# Counter2DigitRG.net
KiCad netlist of a schematic drawn in EAGLE
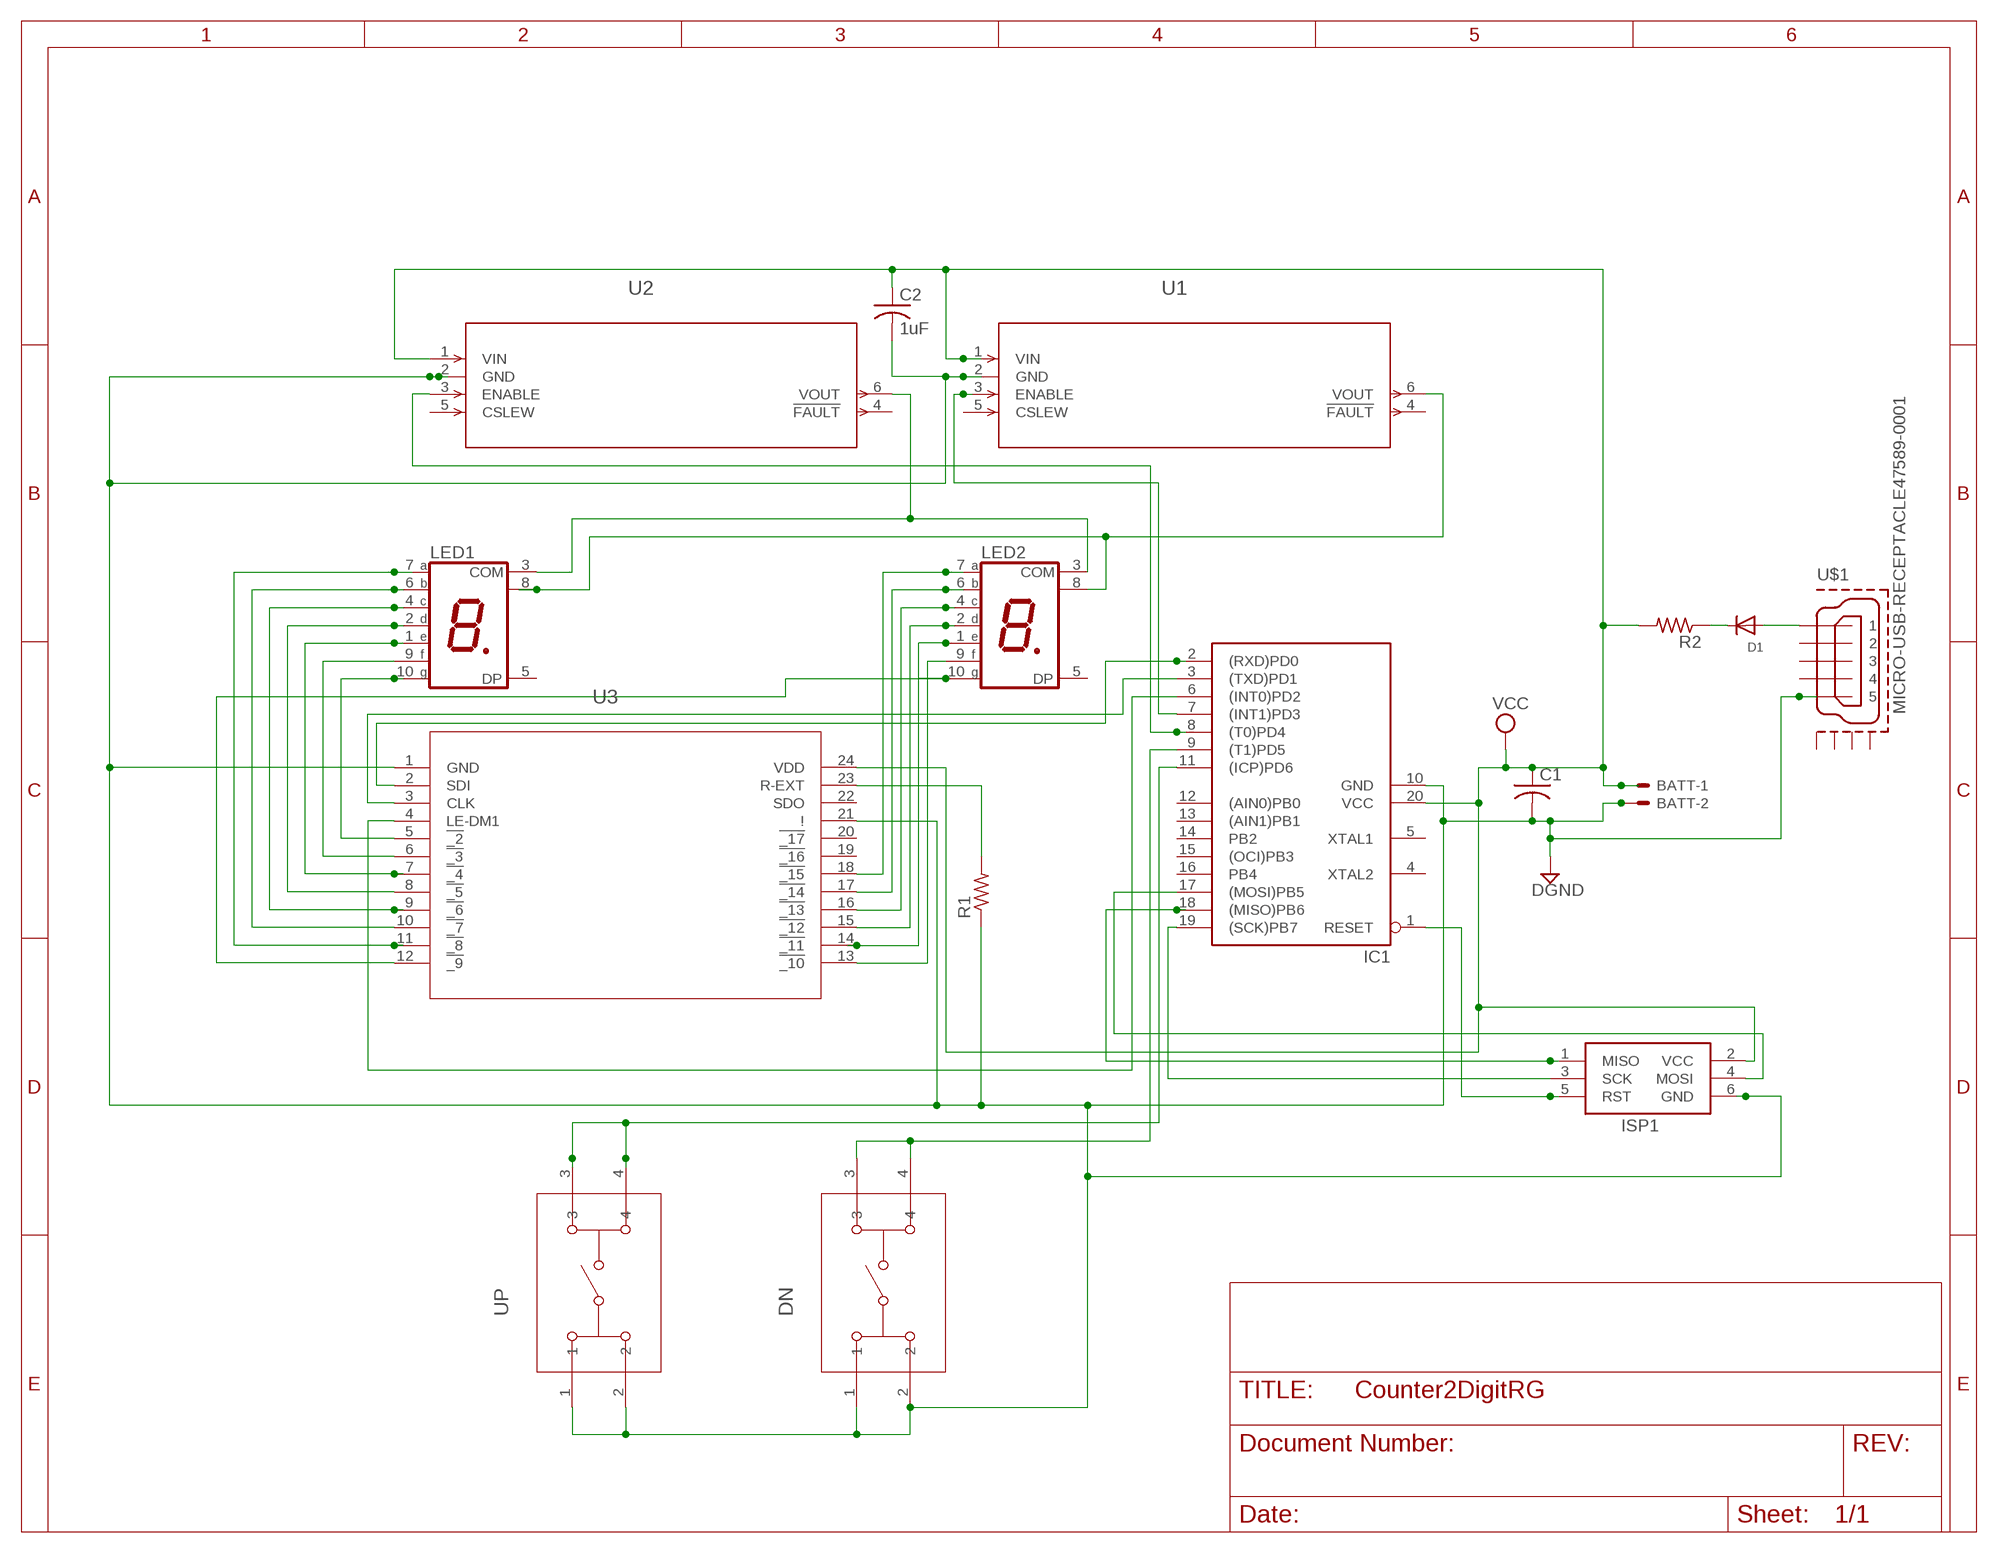
[diagram p0: schematic, sheet 1]

(export (version "E")
  (design (tool "Eeschema 10.0.6"))
  (components
    (comp (ref "BATT")
      (value "22-23-2021")
      (footprint "eagle-import:22-23-2021")
      (fields (field (name "MF") "MOLEX"))
      (libsource (lib "eagle-import") (part "22-23-2021"))
    )
    (comp (ref "C1")
      (value "C-USC0805")
      (footprint "eagle-import:C0805")
      (libsource (lib "eagle-import") (part "C-USC0805"))
    )
    (comp (ref "C2")
      (value "1uF")
      (footprint "eagle-import:C0805")
      (libsource (lib "eagle-import") (part "C-USC0805"))
    )
    (comp (ref "D1")
      (value "DIODESOD-123")
      (footprint "eagle-import:SOD-123")
      (libsource (lib "eagle-import") (part "DIODESOD-123"))
    )
    (comp (ref "DN")
      (value "1-1825910-4")
      (footprint "eagle-import:SW4_1825910-D")
      (fields (field (name "COPYRIGHT") "Copyright (C) 2016 Accelerated Designs. All rights reserved"))
      (libsource (lib "eagle-import") (part "1-1825910-4"))
    )
    (comp (ref "IC1")
      (value "AT90S2313S")
      (footprint "eagle-import:SO20L")
      (libsource (lib "eagle-import") (part "AT90S2313S"))
    )
    (comp (ref "ISP1")
      (value "AVRISP-6")
      (footprint "eagle-import:AVRISP")
      (libsource (lib "eagle-import") (part "AVRISP-6"))
    )
    (comp (ref "LED1")
      (value "7-SEG_SA56-11")
      (footprint "eagle-import:SA56-11")
      (libsource (lib "eagle-import") (part "7-SEG_SA56-11"))
    )
    (comp (ref "LED2")
      (value "7-SEG_SA56-11")
      (footprint "eagle-import:SA56-11")
      (libsource (lib "eagle-import") (part "7-SEG_SA56-11"))
    )
    (comp (ref "R1")
      (value "R-US_M0805")
      (footprint "eagle-import:M0805")
      (libsource (lib "eagle-import") (part "R-US_M0805"))
    )
    (comp (ref "R2")
      (value "R-US_M0805")
      (footprint "eagle-import:M0805")
      (libsource (lib "eagle-import") (part "R-US_M0805"))
    )
    (comp (ref "U$1")
      (value "MICRO-USB-RECEPTACLE47589-0001")
      (footprint "eagle-import:47589-0001")
      (libsource (lib "eagle-import") (part "MICRO-USB-RECEPTACLE47589-0001"))
    )
    (comp (ref "U1")
      (value "MIC2005A-2YM6-TR")
      (footprint "eagle-import:SOT-23-6_M6")
      (fields (field (name "COPYRIGHT") "Copyright (C) 2018 Accelerated Designs. All rights reserved"))
      (libsource (lib "eagle-import") (part "MIC2005A-2YM6-TR"))
    )
    (comp (ref "U2")
      (value "MIC2005A-2YM6-TR")
      (footprint "eagle-import:SOT-23-6_M6")
      (fields (field (name "COPYRIGHT") "Copyright (C) 2018 Accelerated Designs. All rights reserved"))
      (libsource (lib "eagle-import") (part "MIC2005A-2YM6-TR"))
    )
    (comp (ref "U3")
      (value "STP16CPC26MTRSO-24-M")
      (footprint "eagle-import:SO-24-M")
      (fields (field (name "MANUFACTURER_PART_NUMBER") "STP16CPC26MTR"))
      (libsource (lib "eagle-import") (part "STP16CPC26MTRSO-24-M"))
    )
    (comp (ref "UP")
      (value "1-1825910-4")
      (footprint "eagle-import:SW4_1825910-D")
      (fields (field (name "COPYRIGHT") "Copyright (C) 2016 Accelerated Designs. All rights reserved"))
      (libsource (lib "eagle-import") (part "1-1825910-4"))
    )
  )
  (nets
    (net (code "1") (name "DGND") (class "Default")
      (node (ref "BATT") (pin "2") (pinfunction "S_2") (pintype "passive"))
      (node (ref "C1") (pin "2") (pinfunction "2_2") (pintype "passive"))
      (node (ref "C2") (pin "2") (pinfunction "2_2") (pintype "passive"))
      (node (ref "DN") (pin "1") (pinfunction "1_1") (pintype "passive"))
      (node (ref "DN") (pin "2") (pinfunction "2_2") (pintype "passive"))
      (node (ref "IC1") (pin "10") (pinfunction "GND_10") (pintype "power_in"))
      (node (ref "ISP1") (pin "6") (pinfunction "GND_6") (pintype "power_in"))
      (node (ref "R1") (pin "1") (pinfunction "1_1") (pintype "passive"))
      (node (ref "U$1") (pin "5") (pinfunction "5_5") (pintype "input"))
      (node (ref "U1") (pin "2") (pinfunction "GND_2") (pintype "power_in"))
      (node (ref "U2") (pin "2") (pinfunction "GND_2") (pintype "power_in"))
      (node (ref "U3") (pin "1") (pinfunction "GND_1") (pintype "power_in"))
      (node (ref "U3") (pin "21") (pinfunction "~_21") (pintype "input"))
      (node (ref "UP") (pin "1") (pinfunction "1_1") (pintype "passive"))
      (node (ref "UP") (pin "2") (pinfunction "2_2") (pintype "passive"))
    )
    (net (code "2") (name "Net-(D1-PadA)") (class "Default")
      (node (ref "D1") (pin "A") (pinfunction "A_A") (pintype "passive"))
      (node (ref "U$1") (pin "1") (pinfunction "1_1") (pintype "input"))
    )
    (net (code "3") (name "Net-(D1-PadC)") (class "Default")
      (node (ref "D1") (pin "C") (pinfunction "C_C") (pintype "passive"))
      (node (ref "R2") (pin "1") (pinfunction "1_1") (pintype "passive"))
    )
    (net (code "4") (name "Net-(IC1-(ICP)PD6)") (class "Default")
      (node (ref "IC1") (pin "11") (pinfunction "(ICP)PD6_11") (pintype "bidirectional"))
      (node (ref "UP") (pin "3") (pinfunction "3_3") (pintype "passive"))
      (node (ref "UP") (pin "4") (pinfunction "4_4") (pintype "passive"))
    )
    (net (code "5") (name "Net-(IC1-(INT0)PD2)") (class "Default")
      (node (ref "IC1") (pin "6") (pinfunction "(INT0)PD2_6") (pintype "bidirectional"))
      (node (ref "U3") (pin "4") (pinfunction "LE-DM1_4") (pintype "input"))
    )
    (net (code "6") (name "Net-(IC1-(INT1)PD3)") (class "Default")
      (node (ref "IC1") (pin "7") (pinfunction "(INT1)PD3_7") (pintype "bidirectional"))
      (node (ref "U1") (pin "3") (pinfunction "ENABLE_3") (pintype "input"))
    )
    (net (code "7") (name "Net-(IC1-(MISO)PB6)") (class "Default")
      (node (ref "IC1") (pin "18") (pinfunction "(MISO)PB6_18") (pintype "bidirectional"))
      (node (ref "ISP1") (pin "1") (pinfunction "MISO_1") (pintype "input"))
    )
    (net (code "8") (name "Net-(IC1-(MOSI)PB5)") (class "Default")
      (node (ref "IC1") (pin "17") (pinfunction "(MOSI)PB5_17") (pintype "bidirectional"))
      (node (ref "ISP1") (pin "4") (pinfunction "MOSI_4") (pintype "output"))
    )
    (net (code "9") (name "Net-(IC1-(RXD)PD0)") (class "Default")
      (node (ref "IC1") (pin "2") (pinfunction "(RXD)PD0_2") (pintype "bidirectional"))
      (node (ref "U3") (pin "2") (pinfunction "SDI_2") (pintype "input"))
    )
    (net (code "10") (name "Net-(IC1-(SCK)PB7)") (class "Default")
      (node (ref "IC1") (pin "19") (pinfunction "(SCK)PB7_19") (pintype "bidirectional"))
      (node (ref "ISP1") (pin "3") (pinfunction "SCK_3") (pintype "output"))
    )
    (net (code "11") (name "Net-(IC1-(T0)PD4)") (class "Default")
      (node (ref "IC1") (pin "8") (pinfunction "(T0)PD4_8") (pintype "bidirectional"))
      (node (ref "U2") (pin "3") (pinfunction "ENABLE_3") (pintype "input"))
    )
    (net (code "12") (name "Net-(IC1-(T1)PD5)") (class "Default")
      (node (ref "DN") (pin "3") (pinfunction "3_3") (pintype "passive"))
      (node (ref "DN") (pin "4") (pinfunction "4_4") (pintype "passive"))
      (node (ref "IC1") (pin "9") (pinfunction "(T1)PD5_9") (pintype "bidirectional"))
    )
    (net (code "13") (name "Net-(IC1-(TXD)PD1)") (class "Default")
      (node (ref "IC1") (pin "3") (pinfunction "(TXD)PD1_3") (pintype "bidirectional"))
      (node (ref "U3") (pin "3") (pinfunction "CLK_3") (pintype "input"))
    )
    (net (code "14") (name "Net-(IC1-RESET)") (class "Default")
      (node (ref "IC1") (pin "1") (pinfunction "RESET_1") (pintype "bidirectional"))
      (node (ref "ISP1") (pin "5") (pinfunction "RST_5") (pintype "output"))
    )
    (net (code "15") (name "Net-(LED1-A)") (class "Default")
      (node (ref "LED1") (pin "7") (pinfunction "A_7") (pintype "passive"))
      (node (ref "U3") (pin "11") (pinfunction "~{_8}_11") (pintype "output"))
    )
    (net (code "16") (name "Net-(LED1-B)") (class "Default")
      (node (ref "LED1") (pin "6") (pinfunction "B_6") (pintype "passive"))
      (node (ref "U3") (pin "10") (pinfunction "~{_7}_10") (pintype "output"))
    )
    (net (code "17") (name "Net-(LED1-C)") (class "Default")
      (node (ref "LED1") (pin "4") (pinfunction "C_4") (pintype "passive"))
      (node (ref "U3") (pin "9") (pinfunction "~{_6}_9") (pintype "output"))
    )
    (net (code "18") (name "Net-(LED1-D)") (class "Default")
      (node (ref "LED1") (pin "2") (pinfunction "D_2") (pintype "passive"))
      (node (ref "U3") (pin "8") (pinfunction "~{_5}_8") (pintype "output"))
    )
    (net (code "19") (name "Net-(LED1-E)") (class "Default")
      (node (ref "LED1") (pin "1") (pinfunction "E_1") (pintype "passive"))
      (node (ref "U3") (pin "7") (pinfunction "~{_4}_7") (pintype "output"))
    )
    (net (code "20") (name "Net-(LED1-F)") (class "Default")
      (node (ref "LED1") (pin "9") (pinfunction "F_9") (pintype "passive"))
      (node (ref "U3") (pin "6") (pinfunction "~{_3}_6") (pintype "output"))
    )
    (net (code "21") (name "Net-(LED1-G)") (class "Default")
      (node (ref "LED1") (pin "10") (pinfunction "G_10") (pintype "passive"))
      (node (ref "U3") (pin "5") (pinfunction "~{_2}_5") (pintype "output"))
    )
    (net (code "22") (name "Net-(LED2-A)") (class "Default")
      (node (ref "LED2") (pin "7") (pinfunction "A_7") (pintype "passive"))
      (node (ref "U3") (pin "18") (pinfunction "~{_15}_18") (pintype "output"))
    )
    (net (code "23") (name "Net-(LED2-B)") (class "Default")
      (node (ref "LED2") (pin "6") (pinfunction "B_6") (pintype "passive"))
      (node (ref "U3") (pin "17") (pinfunction "~{_14}_17") (pintype "output"))
    )
    (net (code "24") (name "Net-(LED2-C)") (class "Default")
      (node (ref "LED2") (pin "4") (pinfunction "C_4") (pintype "passive"))
      (node (ref "U3") (pin "16") (pinfunction "~{_13}_16") (pintype "output"))
    )
    (net (code "25") (name "Net-(LED2-D)") (class "Default")
      (node (ref "LED2") (pin "2") (pinfunction "D_2") (pintype "passive"))
      (node (ref "U3") (pin "15") (pinfunction "~{_12}_15") (pintype "output"))
    )
    (net (code "26") (name "Net-(LED2-E)") (class "Default")
      (node (ref "LED2") (pin "1") (pinfunction "E_1") (pintype "passive"))
      (node (ref "U3") (pin "14") (pinfunction "~{_11}_14") (pintype "output"))
    )
    (net (code "27") (name "Net-(LED2-F)") (class "Default")
      (node (ref "LED2") (pin "9") (pinfunction "F_9") (pintype "passive"))
      (node (ref "U3") (pin "13") (pinfunction "~{_10}_13") (pintype "output"))
    )
    (net (code "28") (name "Net-(LED2-G)") (class "Default")
      (node (ref "LED2") (pin "10") (pinfunction "G_10") (pintype "passive"))
      (node (ref "U3") (pin "12") (pinfunction "~{_9}_12") (pintype "output"))
    )
    (net (code "29") (name "Net-(U1-VOUT)") (class "Default")
      (node (ref "LED1") (pin "8") (pinfunction "COM_8") (pintype "passive"))
      (node (ref "LED2") (pin "8") (pinfunction "COM_8") (pintype "passive"))
      (node (ref "U1") (pin "6") (pinfunction "VOUT_6") (pintype "output"))
    )
    (net (code "30") (name "Net-(U2-VOUT)") (class "Default")
      (node (ref "LED1") (pin "3") (pinfunction "COM_3") (pintype "passive"))
      (node (ref "LED2") (pin "3") (pinfunction "COM_3") (pintype "passive"))
      (node (ref "U2") (pin "6") (pinfunction "VOUT_6") (pintype "output"))
    )
    (net (code "31") (name "Net-(U3-R-EXT)") (class "Default")
      (node (ref "R1") (pin "2") (pinfunction "2_2") (pintype "passive"))
      (node (ref "U3") (pin "23") (pinfunction "R-EXT_23") (pintype "input"))
    )
    (net (code "32") (name "VCC") (class "Default")
      (node (ref "BATT") (pin "1") (pinfunction "S_1") (pintype "passive"))
      (node (ref "C1") (pin "1") (pinfunction "1_1") (pintype "passive"))
      (node (ref "C2") (pin "1") (pinfunction "1_1") (pintype "passive"))
      (node (ref "IC1") (pin "20") (pinfunction "VCC_20") (pintype "power_in"))
      (node (ref "ISP1") (pin "2") (pinfunction "VCC_2") (pintype "power_in"))
      (node (ref "R2") (pin "2") (pinfunction "2_2") (pintype "passive"))
      (node (ref "U1") (pin "1") (pinfunction "VIN_1") (pintype "input"))
      (node (ref "U2") (pin "1") (pinfunction "VIN_1") (pintype "input"))
      (node (ref "U3") (pin "24") (pinfunction "VDD_24") (pintype "power_in"))
    )
    (net (code "33") (name "unconnected-(IC1-(AIN0)PB0-Pad12)") (class "Default")
      (node (ref "IC1") (pin "12") (pinfunction "(AIN0)PB0_12") (pintype "bidirectional"))
    )
    (net (code "34") (name "unconnected-(IC1-(AIN1)PB1-Pad13)") (class "Default")
      (node (ref "IC1") (pin "13") (pinfunction "(AIN1)PB1_13") (pintype "bidirectional"))
    )
    (net (code "35") (name "unconnected-(IC1-(OCI)PB3-Pad15)") (class "Default")
      (node (ref "IC1") (pin "15") (pinfunction "(OCI)PB3_15") (pintype "bidirectional"))
    )
    (net (code "36") (name "unconnected-(IC1-PB2-Pad14)") (class "Default")
      (node (ref "IC1") (pin "14") (pinfunction "PB2_14") (pintype "bidirectional"))
    )
    (net (code "37") (name "unconnected-(IC1-PB4-Pad16)") (class "Default")
      (node (ref "IC1") (pin "16") (pinfunction "PB4_16") (pintype "bidirectional"))
    )
    (net (code "38") (name "unconnected-(IC1-XTAL1-Pad5)") (class "Default")
      (node (ref "IC1") (pin "5") (pinfunction "XTAL1_5") (pintype "bidirectional"))
    )
    (net (code "39") (name "unconnected-(IC1-XTAL2-Pad4)") (class "Default")
      (node (ref "IC1") (pin "4") (pinfunction "XTAL2_4") (pintype "bidirectional"))
    )
    (net (code "40") (name "unconnected-(LED1-DP-Pad5)") (class "Default")
      (node (ref "LED1") (pin "5") (pinfunction "DP_5") (pintype "passive"))
    )
    (net (code "41") (name "unconnected-(LED2-DP-Pad5)") (class "Default")
      (node (ref "LED2") (pin "5") (pinfunction "DP_5") (pintype "passive"))
    )
    (net (code "42") (name "unconnected-(U$1-GND1-PadCASING1)") (class "Default")
      (node (ref "U$1") (pin "CASING1") (pinfunction "GND1_CASING1") (pintype "bidirectional"))
    )
    (net (code "43") (name "unconnected-(U$1-GND2-PadCASING2)") (class "Default")
      (node (ref "U$1") (pin "CASING2") (pinfunction "GND2_CASING2") (pintype "bidirectional"))
    )
    (net (code "44") (name "unconnected-(U$1-GND3-PadCASING3)") (class "Default")
      (node (ref "U$1") (pin "CASING3") (pinfunction "GND3_CASING3") (pintype "bidirectional"))
    )
    (net (code "45") (name "unconnected-(U$1-GND4-PadCASING4)") (class "Default")
      (node (ref "U$1") (pin "CASING4") (pinfunction "GND4_CASING4") (pintype "bidirectional"))
    )
    (net (code "46") (name "unconnected-(U$1-Pad2)") (class "Default")
      (node (ref "U$1") (pin "2") (pinfunction "2_2") (pintype "input"))
    )
    (net (code "47") (name "unconnected-(U$1-Pad3)") (class "Default")
      (node (ref "U$1") (pin "3") (pinfunction "3_3") (pintype "input"))
    )
    (net (code "48") (name "unconnected-(U$1-Pad4)") (class "Default")
      (node (ref "U$1") (pin "4") (pinfunction "4_4") (pintype "input"))
    )
    (net (code "49") (name "unconnected-(U1-CSLEW-Pad5)") (class "Default")
      (node (ref "U1") (pin "5") (pinfunction "CSLEW_5") (pintype "input"))
    )
    (net (code "50") (name "unconnected-(U1-~{FAULT}-Pad4)") (class "Default")
      (node (ref "U1") (pin "4") (pinfunction "~{FAULT}_4") (pintype "output"))
    )
    (net (code "51") (name "unconnected-(U2-CSLEW-Pad5)") (class "Default")
      (node (ref "U2") (pin "5") (pinfunction "CSLEW_5") (pintype "input"))
    )
    (net (code "52") (name "unconnected-(U2-~{FAULT}-Pad4)") (class "Default")
      (node (ref "U2") (pin "4") (pinfunction "~{FAULT}_4") (pintype "output"))
    )
    (net (code "53") (name "unconnected-(U3-SDO-Pad22)") (class "Default")
      (node (ref "U3") (pin "22") (pinfunction "SDO_22") (pintype "output"))
    )
    (net (code "54") (name "unconnected-(U3-~{_16}-Pad19)") (class "Default")
      (node (ref "U3") (pin "19") (pinfunction "~{_16}_19") (pintype "output"))
    )
    (net (code "55") (name "unconnected-(U3-~{_17}-Pad20)") (class "Default")
      (node (ref "U3") (pin "20") (pinfunction "~{_17}_20") (pintype "output"))
    )
  )
)
